# Esquema.net
KiCad netlist of a schematic drawn in EAGLE
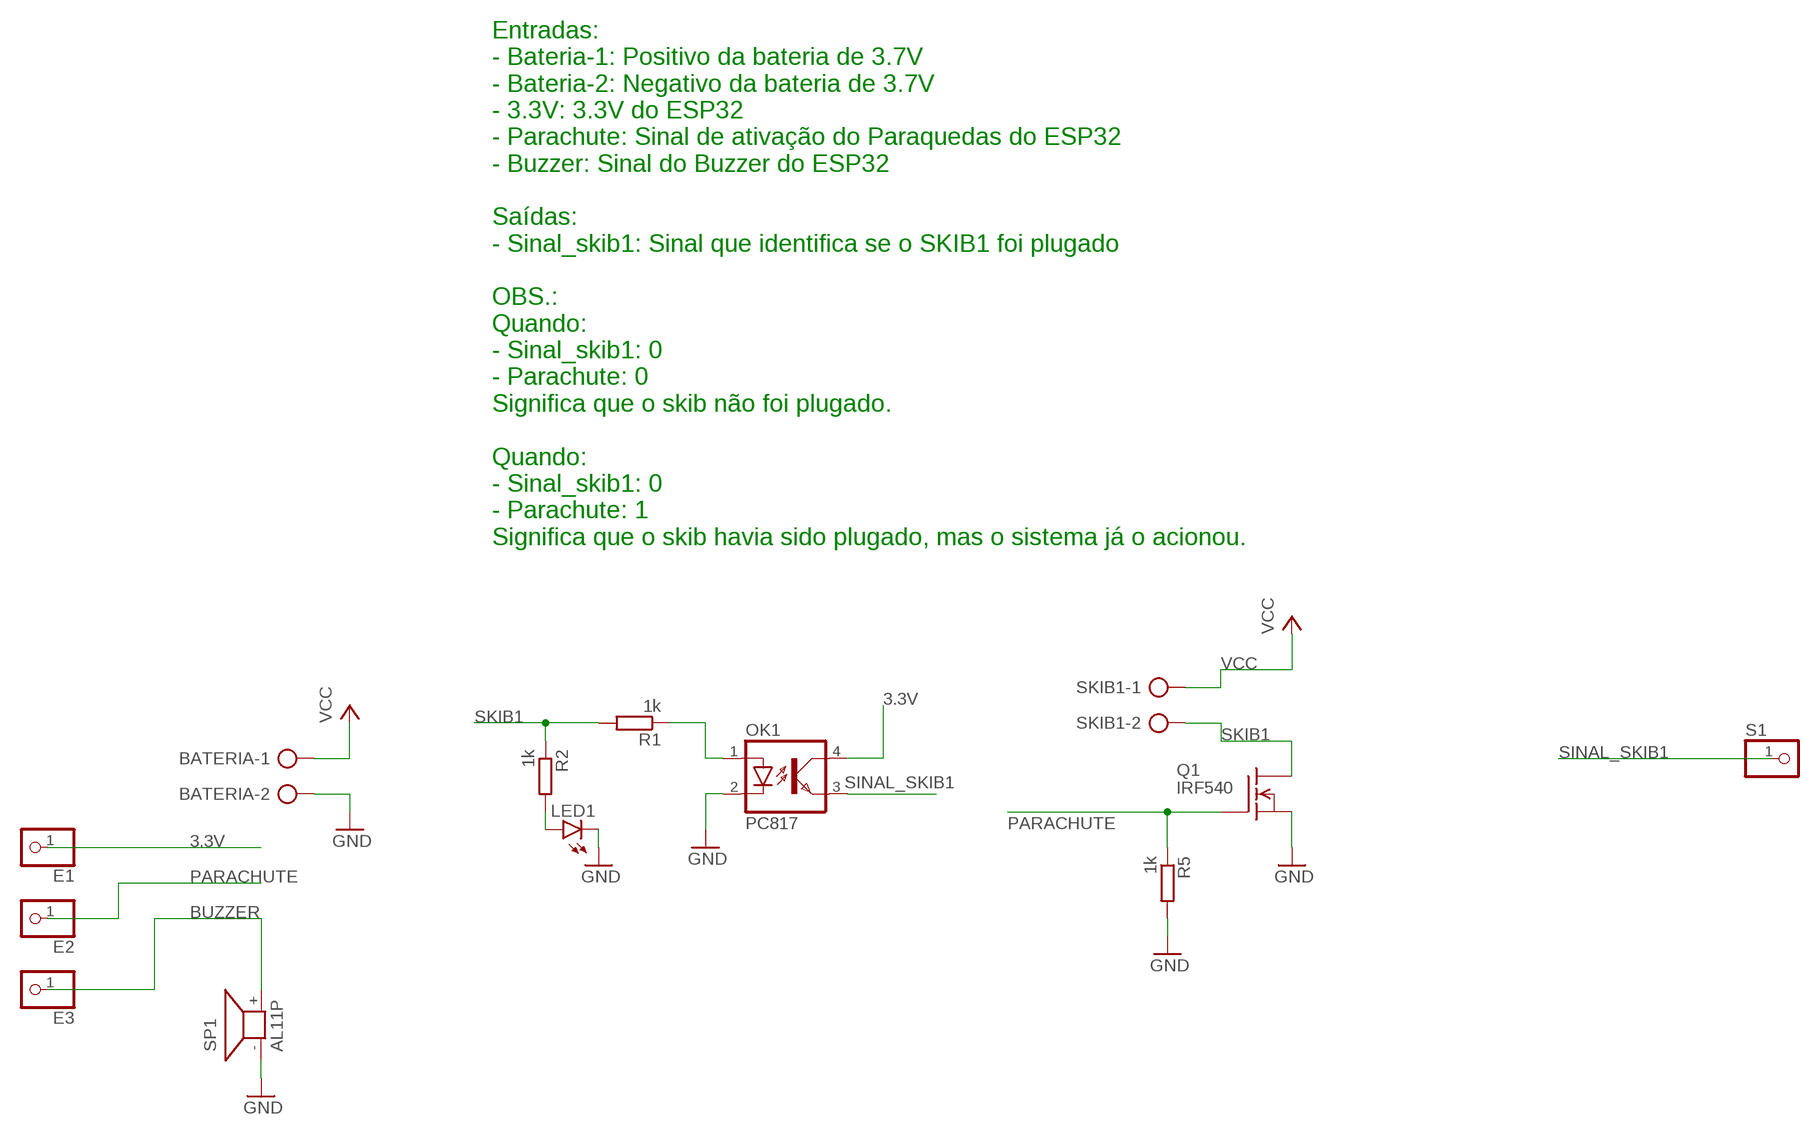
[diagram p0: schematic, sheet 1]

(export (version "E")
  (design (tool "Eeschema 10.0.6"))
  (components
    (comp (ref "BATERIA")
      (value "AK500/2-H")
      (footprint "eagle-import:AK500_2-H")
      (libsource (lib "eagle-import") (part "AK500/2-H"))
    )
    (comp (ref "E1")
      (value "PINHD-1X1")
      (footprint "eagle-import:1X01")
      (libsource (lib "eagle-import") (part "PINHD-1X1"))
    )
    (comp (ref "E2")
      (value "PINHD-1X1")
      (footprint "eagle-import:1X01")
      (libsource (lib "eagle-import") (part "PINHD-1X1"))
    )
    (comp (ref "E3")
      (value "PINHD-1X1")
      (footprint "eagle-import:1X01")
      (libsource (lib "eagle-import") (part "PINHD-1X1"))
    )
    (comp (ref "LED1")
      (value "LED5MM")
      (footprint "eagle-import:LED5MM")
      (libsource (lib "eagle-import") (part "LED5MM"))
    )
    (comp (ref "OK1")
      (value "PC817")
      (footprint "eagle-import:DIL04")
      (fields (field (name "MPN") "PC817X4J000F"))
      (libsource (lib "eagle-import") (part "PC817"))
    )
    (comp (ref "Q1")
      (value "IRF540")
      (footprint "eagle-import:TO220")
      (libsource (lib "eagle-import") (part "IRF540"))
    )
    (comp (ref "R1")
      (value "1k")
      (footprint "eagle-import:0207_10")
      (libsource (lib "eagle-import") (part "R-EU_0207/10"))
    )
    (comp (ref "R2")
      (value "1k")
      (footprint "eagle-import:0207_10")
      (libsource (lib "eagle-import") (part "R-EU_0207/10"))
    )
    (comp (ref "R5")
      (value "1k")
      (footprint "eagle-import:0207_10")
      (libsource (lib "eagle-import") (part "R-EU_0207/10"))
    )
    (comp (ref "S1")
      (value "PINHD-1X1")
      (footprint "eagle-import:1X01")
      (libsource (lib "eagle-import") (part "PINHD-1X1"))
    )
    (comp (ref "SKIB1")
      (value "AK500/2-H")
      (footprint "eagle-import:AK500_2-H")
      (libsource (lib "eagle-import") (part "AK500/2-H"))
    )
    (comp (ref "SP1")
      (value "AL11P")
      (footprint "eagle-import:AL11P")
      (libsource (lib "eagle-import") (part "AL11P"))
    )
  )
  (nets
    (net (code "1") (name "/3.3V") (class "Default")
      (node (ref "E1") (pin "1") (pinfunction "1_1") (pintype "passive"))
      (node (ref "OK1") (pin "4") (pinfunction "COL_4") (pintype "passive"))
    )
    (net (code "2") (name "/BUZZER") (class "Default")
      (node (ref "E3") (pin "1") (pinfunction "1_1") (pintype "passive"))
      (node (ref "SP1") (pin "+") (pinfunction "2_+") (pintype "passive"))
    )
    (net (code "3") (name "/PARACHUTE") (class "Default")
      (node (ref "E2") (pin "1") (pinfunction "1_1") (pintype "passive"))
      (node (ref "Q1") (pin "1") (pinfunction "G_1") (pintype "passive"))
      (node (ref "R5") (pin "1") (pinfunction "1_1") (pintype "passive"))
    )
    (net (code "4") (name "/SINAL_SKIB1") (class "Default")
      (node (ref "OK1") (pin "3") (pinfunction "EMIT_3") (pintype "passive"))
      (node (ref "S1") (pin "1") (pinfunction "1_1") (pintype "passive"))
    )
    (net (code "5") (name "/SKIB1") (class "Default")
      (node (ref "Q1") (pin "2") (pinfunction "D_2") (pintype "passive"))
      (node (ref "R1") (pin "2") (pinfunction "2_2") (pintype "passive"))
      (node (ref "R2") (pin "1") (pinfunction "1_1") (pintype "passive"))
      (node (ref "SKIB1") (pin "2") (pinfunction "KL_2") (pintype "passive"))
    )
    (net (code "6") (name "GND") (class "Default")
      (node (ref "BATERIA") (pin "2") (pinfunction "KL_2") (pintype "passive"))
      (node (ref "LED1") (pin "K") (pinfunction "C_K") (pintype "passive"))
      (node (ref "OK1") (pin "2") (pinfunction "C_2") (pintype "passive"))
      (node (ref "Q1") (pin "3") (pinfunction "S_3") (pintype "passive"))
      (node (ref "R5") (pin "2") (pinfunction "2_2") (pintype "passive"))
      (node (ref "SP1") (pin "-") (pinfunction "1_-") (pintype "passive"))
    )
    (net (code "7") (name "Net-(LED1-PadA)") (class "Default")
      (node (ref "LED1") (pin "A") (pinfunction "A_A") (pintype "passive"))
      (node (ref "R2") (pin "2") (pinfunction "2_2") (pintype "passive"))
    )
    (net (code "8") (name "Net-(OK1-A)") (class "Default")
      (node (ref "OK1") (pin "1") (pinfunction "A_1") (pintype "passive"))
      (node (ref "R1") (pin "1") (pinfunction "1_1") (pintype "passive"))
    )
    (net (code "9") (name "VCC") (class "Default")
      (node (ref "BATERIA") (pin "1") (pinfunction "KL_1") (pintype "passive"))
      (node (ref "SKIB1") (pin "1") (pinfunction "KL_1") (pintype "passive"))
    )
  )
)
